# SCH_Contaier_90mm_2022-04-15.net
KiCad netlist of a schematic drawn in EasyEDA
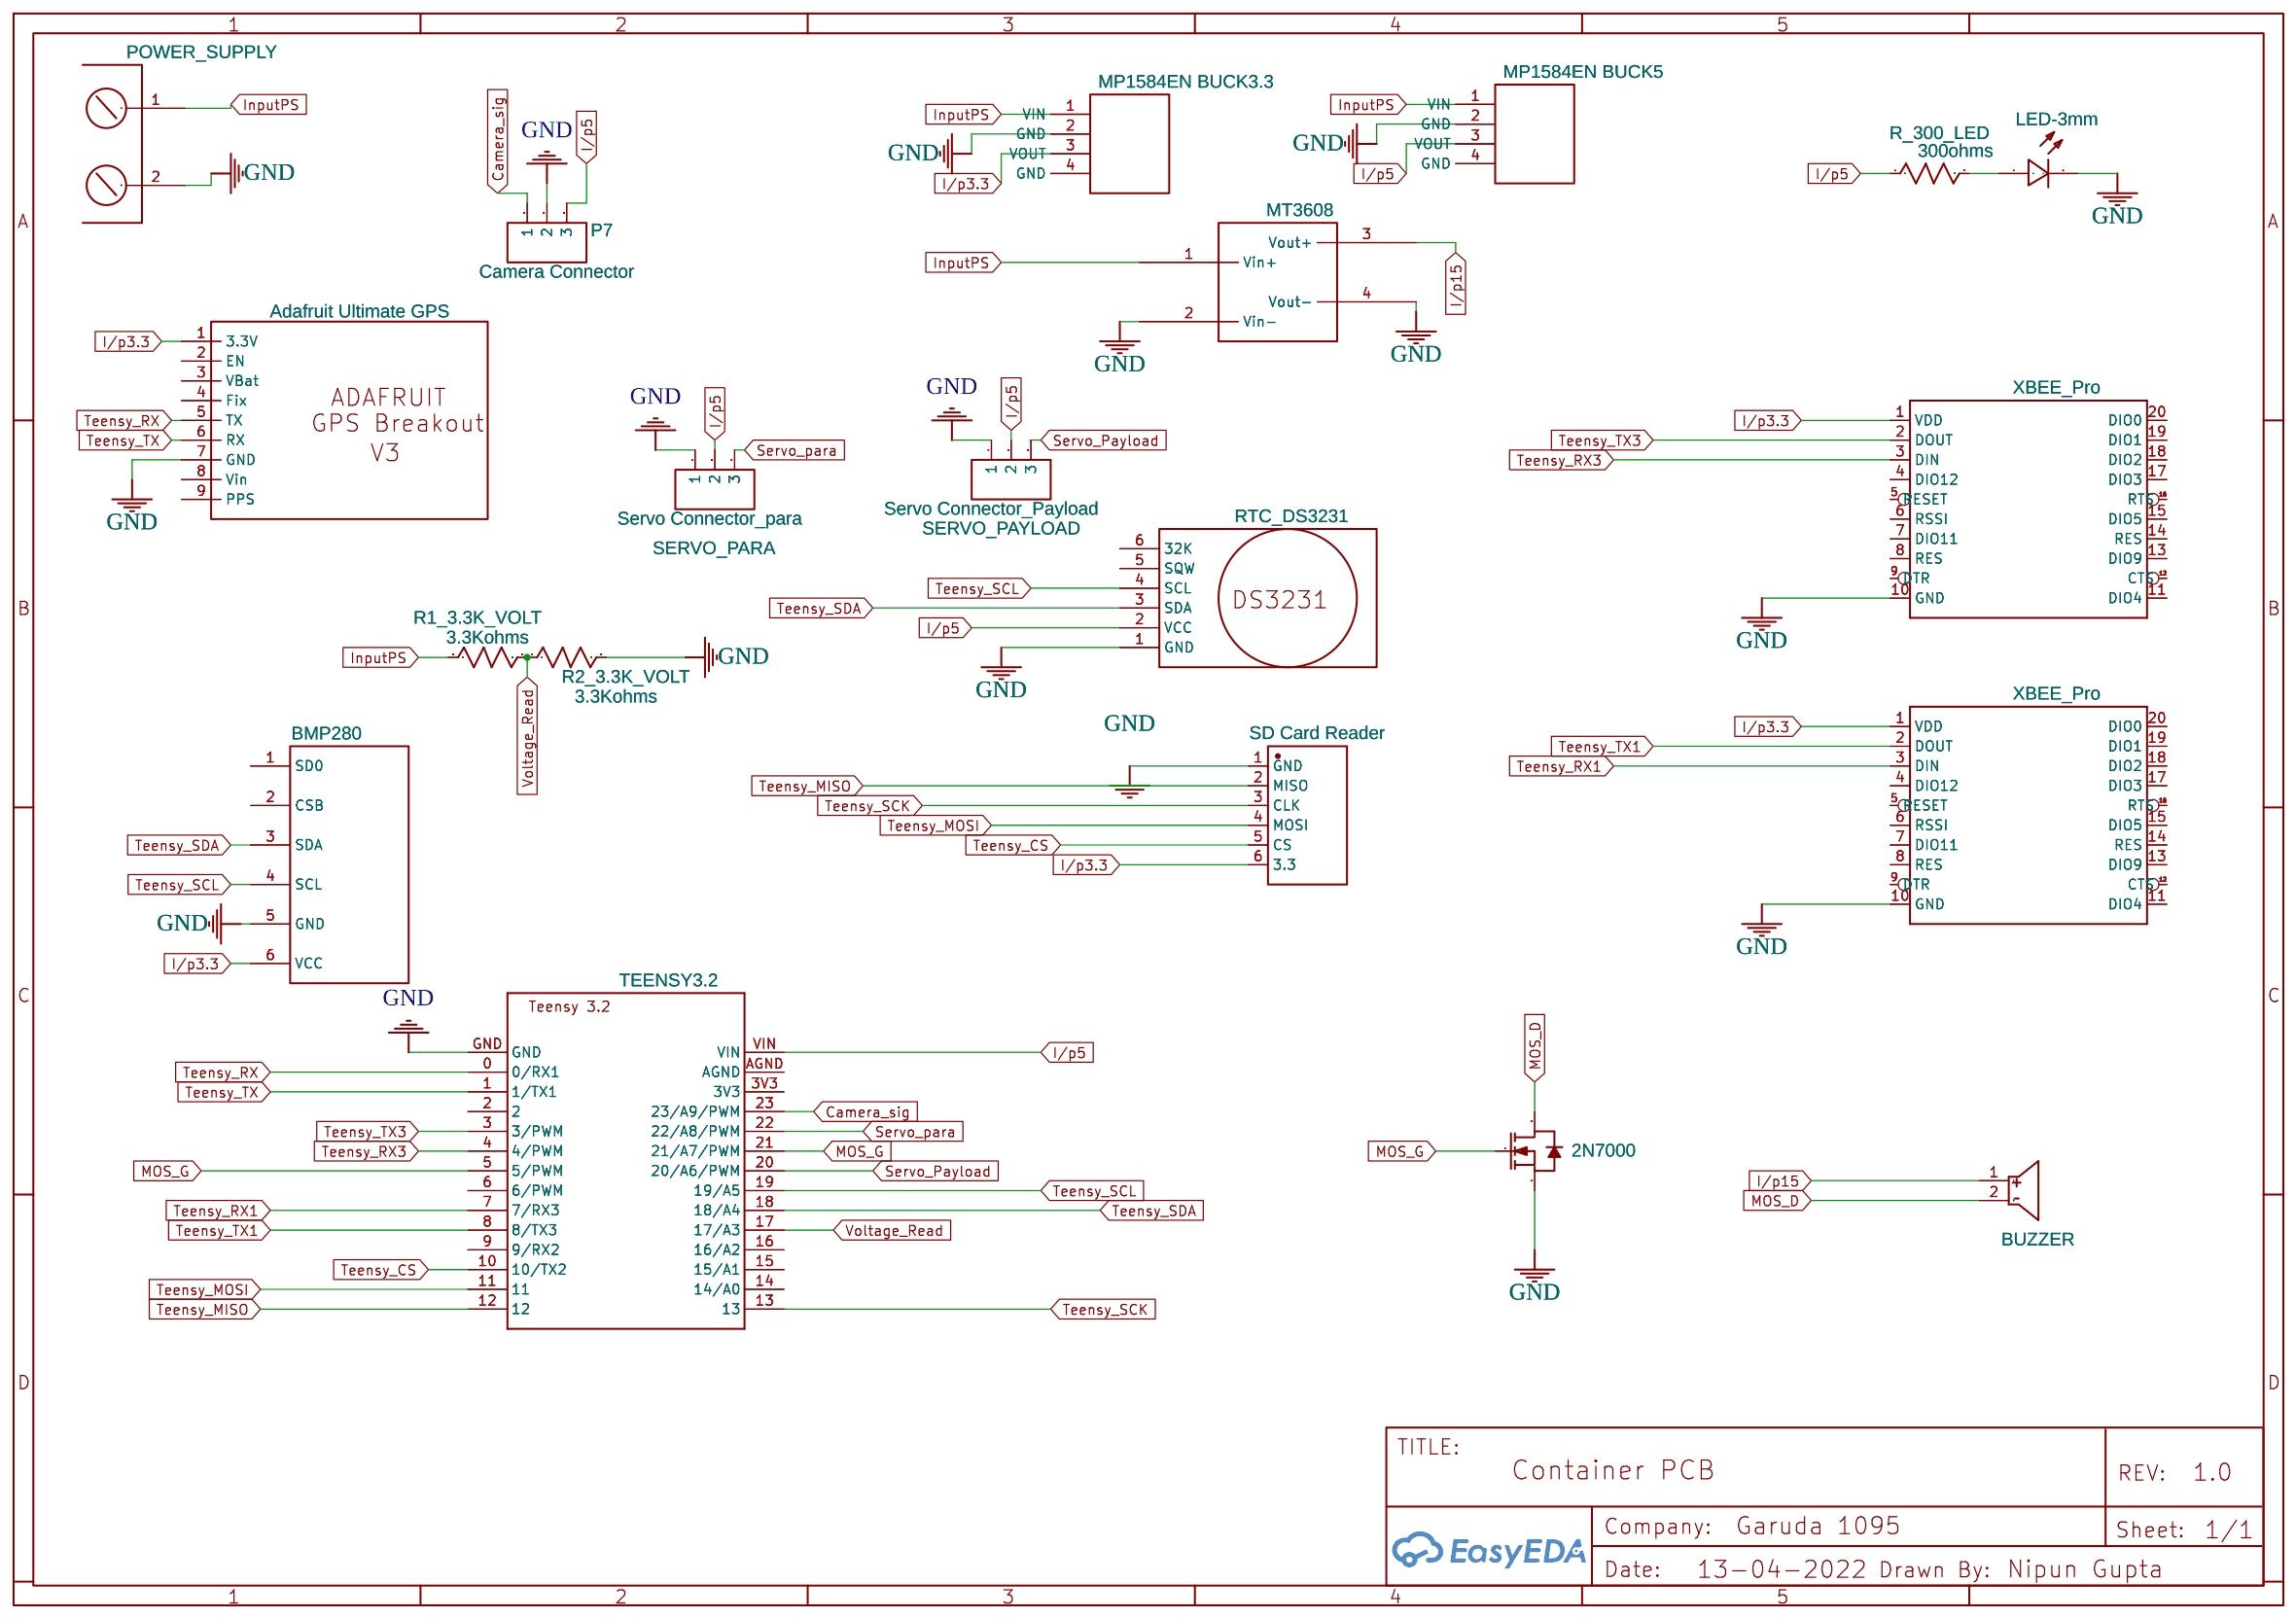
[diagram p0: schematic sheet]

(export (version "E")
  (design (tool "Eeschema 10.0.6"))
  (components
    (comp (ref "BUZZER")
      (value "FMQ-BUZZER2")
      (fields (field (name "BOM_Supplier Part") "C9900006103"))
      (libsource (lib "") (part "FMQ-BUZZER2"))
    )
    (comp (ref "J1") (value "POWER_SUPPLY") (libsource (lib "") (part "2pin_5A_TerminalBlock")))
    (comp (ref "JP2") (value "XBEE_Pro") (libsource (lib "") (part "XBEE_Pro")))
    (comp (ref "JP3") (value "XBEE_Pro") (libsource (lib "") (part "XBEE_Pro")))
    (comp (ref "LED1")
      (value "LED-3mm")
      (fields
        (field (name "BOM_Manufacturer Part") "204-10SURD/S530-A3")
        (field (name "BOM_Supplier Part") "C99772")
      )
      (libsource (lib "") (part "Unknown_1025_-730"))
    )
    (comp (ref "P7")
      (value "Camera Connector")
      (fields
        (field (name "BOM_Manufacturer Part") "Header-Female-2.54_1x3")
        (field (name "BOM_Supplier Part") "C146243")
      )
      (libsource (lib "") (part "Header-Female-2.54_1x3_1"))
    )
    (comp (ref "PRESS1")
      (value "BMP280")
      (fields (field (name "BOM_Manufacturer Part") "?"))
      (libsource (lib "") (part "BMP280 Sparkfun"))
    )
    (comp (ref "Q1")
      (value "2N7000")
      (fields (field (name "BOM_Manufacturer Part") "2N7000BU") (field (name "BOM_Supplier Part") "C896650"))
      (libsource (lib "") (part "2N7000BU"))
    )
    (comp (ref "R1_3.3K_VOLT")
      (value "3.3Kohms")
      (fields (field (name "BOM_Manufacturer Part") "?"))
      (libsource (lib "") (part "Res_AXIAL-0.3(1/8W)_US_2"))
    )
    (comp (ref "R2_3.3K_VOLT")
      (value "3.3Kohms")
      (fields (field (name "BOM_Manufacturer Part") "?"))
      (libsource (lib "") (part "Res_AXIAL-0.3(1/8W)_US_1"))
    )
    (comp (ref "R_300_LED")
      (value "300ohms")
      (fields (field (name "BOM_Manufacturer Part") "?"))
      (libsource (lib "") (part "Res_AXIAL-0.3(1/8W)_US"))
    )
    (comp (ref "SD-READER3")
      (value "SD Card Reader")
      (fields (field (name "BOM_Manufacturer Part") "SD card reader 17.9x17.9"))
      (libsource (lib "") (part "Micro SD Card Reader"))
    )
    (comp (ref "SERVO_PARA")
      (value "Servo Connector_para")
      (fields
        (field (name "BOM_Manufacturer Part") "Header-Female-2.54_1x3")
        (field (name "BOM_Supplier Part") "C146243")
      )
      (libsource (lib "") (part "Header-Female-2.54_1x3_2"))
    )
    (comp (ref "SERVO_PAYLOAD")
      (value "Servo Connector_Payload")
      (fields
        (field (name "BOM_Manufacturer Part") "Header-Female-2.54_1x3")
        (field (name "BOM_Supplier Part") "C146243")
      )
      (libsource (lib "") (part "Header-Female-2.54_1x3"))
    )
    (comp (ref "U1")
      (value "Adafruit Ultimate GPS")
      (fields
        (field (name "BOM_Manufacturer Part") "New SchematicLib")
        (field (name "BOM_Supplier Part") "746")
      )
      (libsource (lib "") (part "Adafruit Ultimate GPS Breakout V3"))
    )
    (comp (ref "U2") (value "MP1584EN BUCK5") (libsource (lib "") (part "MP1584EN COPY")))
    (comp (ref "U3") (value "MP1584EN BUCK3.3") (libsource (lib "") (part "MP1584EN COPY")))
    (comp (ref "U5") (value "TEENSY3.2") (libsource (lib "") (part "TEENSY3.2")))
    (comp (ref "U6") (value "MT3608") (libsource (lib "") (part "MT3608")))
    (comp (ref "U17") (value "RTC_DS3231") (libsource (lib "") (part "UhrModul_DS3231")))
  )
  (nets
    (net (code "1") (name "Camera_sig") (class "Default")
      (node (ref "P7") (pin "1") (pinfunction "1_1") (pintype "input"))
      (node (ref "U5") (pin "23") (pinfunction "23/A9/PWM_23") (pintype "bidirectional"))
    )
    (net (code "2") (name "GND") (class "Default")
      (node (ref "J1") (pin "2") (pinfunction "2_2") (pintype "unspecified"))
      (node (ref "JP2") (pin "10") (pinfunction "GND_10") (pintype "passive"))
      (node (ref "JP3") (pin "10") (pinfunction "GND_10") (pintype "passive"))
      (node (ref "LED1") (pin "2") (pinfunction "-_2") (pintype "unspecified"))
      (node (ref "P7") (pin "2") (pinfunction "2_2") (pintype "input"))
      (node (ref "PRESS1") (pin "5") (pinfunction "GND_5") (pintype "unspecified"))
      (node (ref "Q1") (pin "1") (pinfunction "S_1") (pintype "unspecified"))
      (node (ref "R2_3.3K_VOLT") (pin "2") (pinfunction "2_2") (pintype "unspecified"))
      (node (ref "SD-READER3") (pin "1") (pinfunction "GND_1") (pintype "unspecified"))
      (node (ref "SERVO_PARA") (pin "1") (pinfunction "1_1") (pintype "input"))
      (node (ref "SERVO_PAYLOAD") (pin "1") (pinfunction "1_1") (pintype "input"))
      (node (ref "U1") (pin "7") (pinfunction "GND_7") (pintype "unspecified"))
      (node (ref "U17") (pin "1") (pinfunction "GND_1") (pintype "unspecified"))
      (node (ref "U2") (pin "2") (pinfunction "GND_2") (pintype "unspecified"))
      (node (ref "U3") (pin "2") (pinfunction "GND_2") (pintype "unspecified"))
      (node (ref "U5") (pin "GND") (pinfunction "GND_GND") (pintype "bidirectional"))
      (node (ref "U6") (pin "2") (pinfunction "Vin-_2") (pintype "unspecified"))
      (node (ref "U6") (pin "4") (pinfunction "Vout-_4") (pintype "unspecified"))
    )
    (net (code "3") (name "InputPS") (class "Default")
      (node (ref "J1") (pin "1") (pinfunction "1_1") (pintype "unspecified"))
      (node (ref "R1_3.3K_VOLT") (pin "1") (pinfunction "1_1") (pintype "unspecified"))
      (node (ref "U2") (pin "1") (pinfunction "VIN_1") (pintype "unspecified"))
      (node (ref "U3") (pin "1") (pinfunction "VIN_1") (pintype "unspecified"))
      (node (ref "U6") (pin "1") (pinfunction "Vin+_1") (pintype "unspecified"))
    )
    (net (code "4") (name "I{slash}p3.3") (class "Default")
      (node (ref "JP2") (pin "1") (pinfunction "VDD_1") (pintype "passive"))
      (node (ref "JP3") (pin "1") (pinfunction "VDD_1") (pintype "passive"))
      (node (ref "PRESS1") (pin "6") (pinfunction "VCC_6") (pintype "unspecified"))
      (node (ref "SD-READER3") (pin "6") (pinfunction "3.3_6") (pintype "unspecified"))
      (node (ref "U1") (pin "1") (pinfunction "3.3V_1") (pintype "unspecified"))
      (node (ref "U3") (pin "3") (pinfunction "VOUT_3") (pintype "unspecified"))
    )
    (net (code "5") (name "I{slash}p5") (class "Default")
      (node (ref "P7") (pin "3") (pinfunction "3_3") (pintype "input"))
      (node (ref "R_300_LED") (pin "1") (pinfunction "1_1") (pintype "unspecified"))
      (node (ref "SERVO_PARA") (pin "2") (pinfunction "2_2") (pintype "input"))
      (node (ref "SERVO_PAYLOAD") (pin "2") (pinfunction "2_2") (pintype "input"))
      (node (ref "U17") (pin "2") (pinfunction "VCC_2") (pintype "unspecified"))
      (node (ref "U2") (pin "3") (pinfunction "VOUT_3") (pintype "unspecified"))
      (node (ref "U5") (pin "VIN") (pinfunction "VIN_VIN") (pintype "bidirectional"))
    )
    (net (code "6") (name "I{slash}p15") (class "Default")
      (node (ref "BUZZER") (pin "1") (pinfunction "1_1") (pintype "unspecified"))
      (node (ref "U6") (pin "3") (pinfunction "Vout+_3") (pintype "unspecified"))
    )
    (net (code "7") (name "MOS_D") (class "Default")
      (node (ref "BUZZER") (pin "2") (pinfunction "2_2") (pintype "unspecified"))
      (node (ref "Q1") (pin "3") (pinfunction "D_3") (pintype "unspecified"))
    )
    (net (code "8") (name "MOS_G") (class "Default")
      (node (ref "Q1") (pin "2") (pinfunction "G_2") (pintype "unspecified"))
      (node (ref "U5") (pin "21") (pinfunction "21/A7/PWM_21") (pintype "bidirectional"))
      (node (ref "U5") (pin "5") (pinfunction "5/PWM_5") (pintype "bidirectional"))
    )
    (net (code "9") (name "Net-(LED1-+)") (class "Default")
      (node (ref "LED1") (pin "1") (pinfunction "+_1") (pintype "unspecified"))
      (node (ref "R_300_LED") (pin "2") (pinfunction "2_2") (pintype "unspecified"))
    )
    (net (code "10") (name "Servo_Payload") (class "Default")
      (node (ref "SERVO_PAYLOAD") (pin "3") (pinfunction "3_3") (pintype "input"))
      (node (ref "U5") (pin "20") (pinfunction "20/A6/PWM_20") (pintype "bidirectional"))
    )
    (net (code "11") (name "Servo_para") (class "Default")
      (node (ref "SERVO_PARA") (pin "3") (pinfunction "3_3") (pintype "input"))
      (node (ref "U5") (pin "22") (pinfunction "22/A8/PWM_22") (pintype "bidirectional"))
    )
    (net (code "12") (name "Teensy_CS") (class "Default")
      (node (ref "SD-READER3") (pin "5") (pinfunction "CS_5") (pintype "unspecified"))
      (node (ref "U5") (pin "10") (pinfunction "10/TX2_10") (pintype "bidirectional"))
    )
    (net (code "13") (name "Teensy_MISO") (class "Default")
      (node (ref "SD-READER3") (pin "2") (pinfunction "MISO_2") (pintype "unspecified"))
      (node (ref "U5") (pin "12") (pinfunction "12_12") (pintype "bidirectional"))
    )
    (net (code "14") (name "Teensy_MOSI") (class "Default")
      (node (ref "SD-READER3") (pin "4") (pinfunction "MOSI_4") (pintype "unspecified"))
      (node (ref "U5") (pin "11") (pinfunction "11_11") (pintype "bidirectional"))
    )
    (net (code "15") (name "Teensy_RX") (class "Default")
      (node (ref "U1") (pin "5") (pinfunction "TX_5") (pintype "unspecified"))
      (node (ref "U5") (pin "0") (pinfunction "0/RX1_0") (pintype "bidirectional"))
    )
    (net (code "16") (name "Teensy_RX1") (class "Default")
      (node (ref "JP2") (pin "3") (pinfunction "DIN_3") (pintype "input"))
      (node (ref "U5") (pin "7") (pinfunction "7/RX3_7") (pintype "bidirectional"))
    )
    (net (code "17") (name "Teensy_RX3") (class "Default")
      (node (ref "JP3") (pin "3") (pinfunction "DIN_3") (pintype "input"))
      (node (ref "U5") (pin "4") (pinfunction "4/PWM_4") (pintype "bidirectional"))
    )
    (net (code "18") (name "Teensy_SCK") (class "Default")
      (node (ref "SD-READER3") (pin "3") (pinfunction "CLK_3") (pintype "unspecified"))
      (node (ref "U5") (pin "13") (pinfunction "13_13") (pintype "bidirectional"))
    )
    (net (code "19") (name "Teensy_SCL") (class "Default")
      (node (ref "PRESS1") (pin "4") (pinfunction "SCL_4") (pintype "unspecified"))
      (node (ref "U17") (pin "4") (pinfunction "SCL_4") (pintype "unspecified"))
      (node (ref "U5") (pin "19") (pinfunction "19/A5_19") (pintype "bidirectional"))
    )
    (net (code "20") (name "Teensy_SDA") (class "Default")
      (node (ref "PRESS1") (pin "3") (pinfunction "SDA_3") (pintype "unspecified"))
      (node (ref "U17") (pin "3") (pinfunction "SDA_3") (pintype "unspecified"))
      (node (ref "U5") (pin "18") (pinfunction "18/A4_18") (pintype "bidirectional"))
    )
    (net (code "21") (name "Teensy_TX") (class "Default")
      (node (ref "U1") (pin "6") (pinfunction "RX_6") (pintype "unspecified"))
      (node (ref "U5") (pin "1") (pinfunction "1/TX1_1") (pintype "bidirectional"))
    )
    (net (code "22") (name "Teensy_TX1") (class "Default")
      (node (ref "JP2") (pin "2") (pinfunction "DOUT_2") (pintype "output"))
      (node (ref "U5") (pin "8") (pinfunction "8/TX3_8") (pintype "bidirectional"))
    )
    (net (code "23") (name "Teensy_TX3") (class "Default")
      (node (ref "JP3") (pin "2") (pinfunction "DOUT_2") (pintype "output"))
      (node (ref "U5") (pin "3") (pinfunction "3/PWM_3") (pintype "bidirectional"))
    )
    (net (code "24") (name "Voltage_Read") (class "Default")
      (node (ref "R1_3.3K_VOLT") (pin "2") (pinfunction "2_2") (pintype "unspecified"))
      (node (ref "R2_3.3K_VOLT") (pin "1") (pinfunction "1_1") (pintype "unspecified"))
      (node (ref "U5") (pin "17") (pinfunction "17/A3_17") (pintype "bidirectional"))
    )
    (net (code "25") (name "unconnected-(JP2-CTS-Pad12)") (class "Default")
      (node (ref "JP2") (pin "12") (pinfunction "CTS_12") (pintype "output"))
    )
    (net (code "26") (name "unconnected-(JP2-DIO0-Pad20)") (class "Default")
      (node (ref "JP2") (pin "20") (pinfunction "DIO0_20") (pintype "unspecified"))
    )
    (net (code "27") (name "unconnected-(JP2-DIO1-Pad19)") (class "Default")
      (node (ref "JP2") (pin "19") (pinfunction "DIO1_19") (pintype "unspecified"))
    )
    (net (code "28") (name "unconnected-(JP2-DIO2-Pad18)") (class "Default")
      (node (ref "JP2") (pin "18") (pinfunction "DIO2_18") (pintype "unspecified"))
    )
    (net (code "29") (name "unconnected-(JP2-DIO3-Pad17)") (class "Default")
      (node (ref "JP2") (pin "17") (pinfunction "DIO3_17") (pintype "unspecified"))
    )
    (net (code "30") (name "unconnected-(JP2-DIO4-Pad11)") (class "Default")
      (node (ref "JP2") (pin "11") (pinfunction "DIO4_11") (pintype "unspecified"))
    )
    (net (code "31") (name "unconnected-(JP2-DIO5-Pad15)") (class "Default")
      (node (ref "JP2") (pin "15") (pinfunction "DIO5_15") (pintype "unspecified"))
    )
    (net (code "32") (name "unconnected-(JP2-DIO9-Pad13)") (class "Default")
      (node (ref "JP2") (pin "13") (pinfunction "DIO9_13") (pintype "unspecified"))
    )
    (net (code "33") (name "unconnected-(JP2-DIO11-Pad7)") (class "Default")
      (node (ref "JP2") (pin "7") (pinfunction "DIO11_7") (pintype "unspecified"))
    )
    (net (code "34") (name "unconnected-(JP2-DIO12-Pad4)") (class "Default")
      (node (ref "JP2") (pin "4") (pinfunction "DIO12_4") (pintype "unspecified"))
    )
    (net (code "35") (name "unconnected-(JP2-DTR-Pad9)") (class "Default")
      (node (ref "JP2") (pin "9") (pinfunction "DTR_9") (pintype "unspecified"))
    )
    (net (code "36") (name "unconnected-(JP2-RES-Pad8)") (class "Default")
      (node (ref "JP2") (pin "8") (pinfunction "RES_8") (pintype "unspecified"))
    )
    (net (code "37") (name "unconnected-(JP2-RES-Pad14)") (class "Default")
      (node (ref "JP2") (pin "14") (pinfunction "RES_14") (pintype "unspecified"))
    )
    (net (code "38") (name "unconnected-(JP2-RESET-Pad5)") (class "Default")
      (node (ref "JP2") (pin "5") (pinfunction "RESET_5") (pintype "input"))
    )
    (net (code "39") (name "unconnected-(JP2-RSSI-Pad6)") (class "Default")
      (node (ref "JP2") (pin "6") (pinfunction "RSSI_6") (pintype "unspecified"))
    )
    (net (code "40") (name "unconnected-(JP2-RTS-Pad16)") (class "Default")
      (node (ref "JP2") (pin "16") (pinfunction "RTS_16") (pintype "input"))
    )
    (net (code "41") (name "unconnected-(JP3-CTS-Pad12)") (class "Default")
      (node (ref "JP3") (pin "12") (pinfunction "CTS_12") (pintype "output"))
    )
    (net (code "42") (name "unconnected-(JP3-DIO0-Pad20)") (class "Default")
      (node (ref "JP3") (pin "20") (pinfunction "DIO0_20") (pintype "unspecified"))
    )
    (net (code "43") (name "unconnected-(JP3-DIO1-Pad19)") (class "Default")
      (node (ref "JP3") (pin "19") (pinfunction "DIO1_19") (pintype "unspecified"))
    )
    (net (code "44") (name "unconnected-(JP3-DIO2-Pad18)") (class "Default")
      (node (ref "JP3") (pin "18") (pinfunction "DIO2_18") (pintype "unspecified"))
    )
    (net (code "45") (name "unconnected-(JP3-DIO3-Pad17)") (class "Default")
      (node (ref "JP3") (pin "17") (pinfunction "DIO3_17") (pintype "unspecified"))
    )
    (net (code "46") (name "unconnected-(JP3-DIO4-Pad11)") (class "Default")
      (node (ref "JP3") (pin "11") (pinfunction "DIO4_11") (pintype "unspecified"))
    )
    (net (code "47") (name "unconnected-(JP3-DIO5-Pad15)") (class "Default")
      (node (ref "JP3") (pin "15") (pinfunction "DIO5_15") (pintype "unspecified"))
    )
    (net (code "48") (name "unconnected-(JP3-DIO9-Pad13)") (class "Default")
      (node (ref "JP3") (pin "13") (pinfunction "DIO9_13") (pintype "unspecified"))
    )
    (net (code "49") (name "unconnected-(JP3-DIO11-Pad7)") (class "Default")
      (node (ref "JP3") (pin "7") (pinfunction "DIO11_7") (pintype "unspecified"))
    )
    (net (code "50") (name "unconnected-(JP3-DIO12-Pad4)") (class "Default")
      (node (ref "JP3") (pin "4") (pinfunction "DIO12_4") (pintype "unspecified"))
    )
    (net (code "51") (name "unconnected-(JP3-DTR-Pad9)") (class "Default")
      (node (ref "JP3") (pin "9") (pinfunction "DTR_9") (pintype "unspecified"))
    )
    (net (code "52") (name "unconnected-(JP3-RES-Pad8)") (class "Default")
      (node (ref "JP3") (pin "8") (pinfunction "RES_8") (pintype "unspecified"))
    )
    (net (code "53") (name "unconnected-(JP3-RES-Pad14)") (class "Default")
      (node (ref "JP3") (pin "14") (pinfunction "RES_14") (pintype "unspecified"))
    )
    (net (code "54") (name "unconnected-(JP3-RESET-Pad5)") (class "Default")
      (node (ref "JP3") (pin "5") (pinfunction "RESET_5") (pintype "input"))
    )
    (net (code "55") (name "unconnected-(JP3-RSSI-Pad6)") (class "Default")
      (node (ref "JP3") (pin "6") (pinfunction "RSSI_6") (pintype "unspecified"))
    )
    (net (code "56") (name "unconnected-(JP3-RTS-Pad16)") (class "Default")
      (node (ref "JP3") (pin "16") (pinfunction "RTS_16") (pintype "input"))
    )
    (net (code "57") (name "unconnected-(PRESS1-CSB-Pad2)") (class "Default")
      (node (ref "PRESS1") (pin "2") (pinfunction "CSB_2") (pintype "unspecified"))
    )
    (net (code "58") (name "unconnected-(PRESS1-SD0-Pad1)") (class "Default")
      (node (ref "PRESS1") (pin "1") (pinfunction "SD0_1") (pintype "unspecified"))
    )
    (net (code "59") (name "unconnected-(U1-EN-Pad2)") (class "Default")
      (node (ref "U1") (pin "2") (pinfunction "EN_2") (pintype "unspecified"))
    )
    (net (code "60") (name "unconnected-(U1-Fix-Pad4)") (class "Default")
      (node (ref "U1") (pin "4") (pinfunction "Fix_4") (pintype "unspecified"))
    )
    (net (code "61") (name "unconnected-(U1-PPS-Pad9)") (class "Default")
      (node (ref "U1") (pin "9") (pinfunction "PPS_9") (pintype "unspecified"))
    )
    (net (code "62") (name "unconnected-(U1-VBat-Pad3)") (class "Default")
      (node (ref "U1") (pin "3") (pinfunction "VBat_3") (pintype "unspecified"))
    )
    (net (code "63") (name "unconnected-(U1-Vin-Pad8)") (class "Default")
      (node (ref "U1") (pin "8") (pinfunction "Vin_8") (pintype "unspecified"))
    )
    (net (code "64") (name "unconnected-(U2-GND-Pad4)") (class "Default")
      (node (ref "U2") (pin "4") (pinfunction "GND_4") (pintype "unspecified"))
    )
    (net (code "65") (name "unconnected-(U3-GND-Pad4)") (class "Default")
      (node (ref "U3") (pin "4") (pinfunction "GND_4") (pintype "unspecified"))
    )
    (net (code "66") (name "unconnected-(U5-6{slash}PWM-Pad6)") (class "Default")
      (node (ref "U5") (pin "6") (pinfunction "6/PWM_6") (pintype "bidirectional"))
    )
    (net (code "67") (name "unconnected-(U5-9{slash}RX2-Pad9)") (class "Default")
      (node (ref "U5") (pin "9") (pinfunction "9/RX2_9") (pintype "bidirectional"))
    )
    (net (code "68") (name "unconnected-(U5-14{slash}A0-Pad14)") (class "Default")
      (node (ref "U5") (pin "14") (pinfunction "14/A0_14") (pintype "bidirectional"))
    )
    (net (code "69") (name "unconnected-(U5-15{slash}A1-Pad15)") (class "Default")
      (node (ref "U5") (pin "15") (pinfunction "15/A1_15") (pintype "bidirectional"))
    )
    (net (code "70") (name "unconnected-(U5-16{slash}A2-Pad16)") (class "Default")
      (node (ref "U5") (pin "16") (pinfunction "16/A2_16") (pintype "bidirectional"))
    )
    (net (code "71") (name "unconnected-(U5-Pad2)") (class "Default")
      (node (ref "U5") (pin "2") (pinfunction "2_2") (pintype "bidirectional"))
    )
    (net (code "72") (name "unconnected-(U5-Pad3V3)") (class "Default")
      (node (ref "U5") (pin "3V3") (pinfunction "3V3_3V3") (pintype "bidirectional"))
    )
    (net (code "73") (name "unconnected-(U5-PadAGND)") (class "Default")
      (node (ref "U5") (pin "AGND") (pinfunction "AGND_AGND") (pintype "bidirectional"))
    )
    (net (code "74") (name "unconnected-(U17-32K-Pad6)") (class "Default")
      (node (ref "U17") (pin "6") (pinfunction "32K_6") (pintype "unspecified"))
    )
    (net (code "75") (name "unconnected-(U17-SQW-Pad5)") (class "Default")
      (node (ref "U17") (pin "5") (pinfunction "SQW_5") (pintype "unspecified"))
    )
  )
)
